# deska.net
KiCad netlist of a schematic drawn in EAGLE
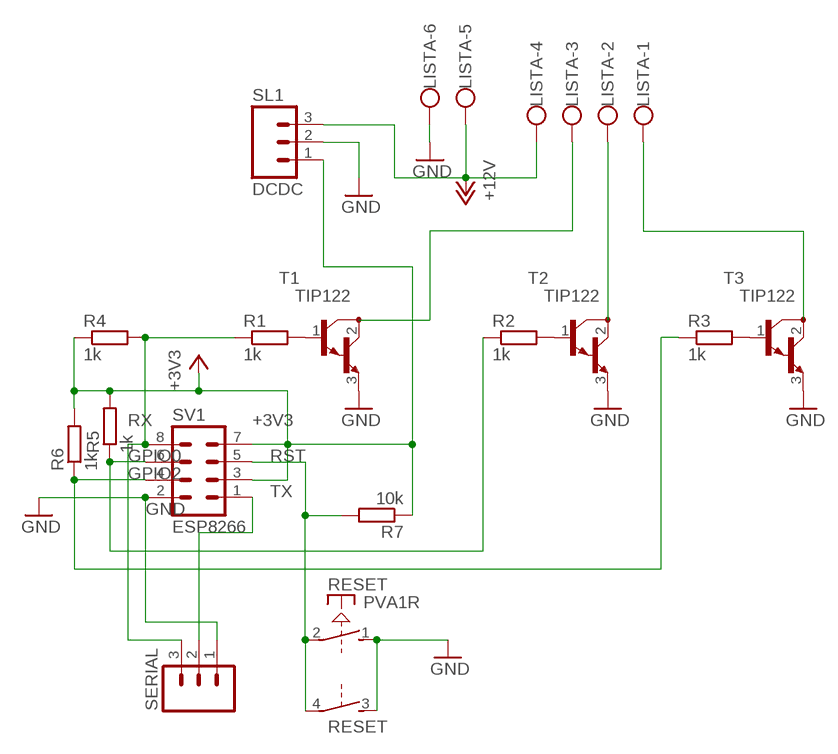
[diagram p0: schematic, sheet 1]

(export (version "E")
  (design (tool "Eeschema 10.0.6"))
  (components
    (comp (ref "LISTA")
      (value "W237-6")
      (footprint "eagle-import:W237-6")
      (libsource (lib "eagle-import") (part "W237-6"))
    )
    (comp (ref "R1")
      (value "1k")
      (footprint "eagle-import:0207_10")
      (libsource (lib "eagle-import") (part "R-EU_0207/10"))
    )
    (comp (ref "R2")
      (value "1k")
      (footprint "eagle-import:0207_10")
      (libsource (lib "eagle-import") (part "R-EU_0207/10"))
    )
    (comp (ref "R3")
      (value "1k")
      (footprint "eagle-import:0207_10")
      (libsource (lib "eagle-import") (part "R-EU_0207/10"))
    )
    (comp (ref "R4")
      (value "1k")
      (footprint "eagle-import:0207_10")
      (libsource (lib "eagle-import") (part "R-EU_0207/10"))
    )
    (comp (ref "R5")
      (value "1k")
      (footprint "eagle-import:0207_10")
      (libsource (lib "eagle-import") (part "R-EU_0207/10"))
    )
    (comp (ref "R6")
      (value "1k")
      (footprint "eagle-import:0207_10")
      (libsource (lib "eagle-import") (part "R-EU_0207/10"))
    )
    (comp (ref "R7")
      (value "10k")
      (footprint "eagle-import:0207_10")
      (libsource (lib "eagle-import") (part "R-EU_0207/10"))
    )
    (comp (ref "RESET")
      (value "PVA1R")
      (footprint "eagle-import:PVA1R")
      (libsource (lib "eagle-import") (part "PVA1R"))
    )
    (comp (ref "SERIAL")
      (value "M03")
      (footprint "eagle-import:03P")
      (libsource (lib "eagle-import") (part "M03"))
    )
    (comp (ref "SL1")
      (value "DCDC")
      (footprint "eagle-import:03P")
      (libsource (lib "eagle-import") (part "M03"))
    )
    (comp (ref "SV1")
      (value "ESP8266")
      (footprint "eagle-import:MA04-2")
      (libsource (lib "eagle-import") (part "MA04-2"))
    )
    (comp (ref "T1")
      (value "TIP122")
      (footprint "eagle-import:TO220")
      (libsource (lib "eagle-import") (part "TIP122"))
    )
    (comp (ref "T2")
      (value "TIP122")
      (footprint "eagle-import:TO220")
      (libsource (lib "eagle-import") (part "TIP122"))
    )
    (comp (ref "T3")
      (value "TIP122")
      (footprint "eagle-import:TO220")
      (libsource (lib "eagle-import") (part "TIP122"))
    )
  )
  (nets
    (net (code "1") (name "+3V3") (class "Default")
      (node (ref "R4") (pin "1") (pinfunction "1_1") (pintype "passive"))
      (node (ref "R5") (pin "2") (pinfunction "2_2") (pintype "passive"))
      (node (ref "R6") (pin "2") (pinfunction "2_2") (pintype "passive"))
      (node (ref "R7") (pin "1") (pinfunction "1_1") (pintype "passive"))
      (node (ref "SL1") (pin "1") (pinfunction "1_1") (pintype "passive"))
      (node (ref "SV1") (pin "3") (pinfunction "3_3") (pintype "passive"))
      (node (ref "SV1") (pin "7") (pinfunction "7_7") (pintype "passive"))
    )
    (net (code "2") (name "+12V") (class "Default")
      (node (ref "LISTA") (pin "4") (pinfunction "KL_4") (pintype "passive"))
      (node (ref "LISTA") (pin "5") (pinfunction "KL_5") (pintype "passive"))
      (node (ref "SL1") (pin "3") (pinfunction "3_3") (pintype "passive"))
    )
    (net (code "3") (name "/GPIO0") (class "Default")
      (node (ref "R2") (pin "1") (pinfunction "1_1") (pintype "passive"))
      (node (ref "R5") (pin "1") (pinfunction "1_1") (pintype "passive"))
      (node (ref "SV1") (pin "6") (pinfunction "6_6") (pintype "passive"))
    )
    (net (code "4") (name "/GPIO2") (class "Default")
      (node (ref "R3") (pin "1") (pinfunction "1_1") (pintype "passive"))
      (node (ref "R6") (pin "1") (pinfunction "1_1") (pintype "passive"))
      (node (ref "SV1") (pin "4") (pinfunction "4_4") (pintype "passive"))
    )
    (net (code "5") (name "/RST") (class "Default")
      (node (ref "R7") (pin "2") (pinfunction "2_2") (pintype "passive"))
      (node (ref "RESET") (pin "2") (pinfunction "P_2") (pintype "passive"))
      (node (ref "RESET") (pin "4") (pinfunction "P_4") (pintype "passive"))
      (node (ref "SV1") (pin "5") (pinfunction "5_5") (pintype "passive"))
    )
    (net (code "6") (name "/RX") (class "Default")
      (node (ref "R1") (pin "1") (pinfunction "1_1") (pintype "passive"))
      (node (ref "R4") (pin "2") (pinfunction "2_2") (pintype "passive"))
      (node (ref "SERIAL") (pin "3") (pinfunction "3_3") (pintype "passive"))
      (node (ref "SV1") (pin "8") (pinfunction "8_8") (pintype "passive"))
    )
    (net (code "7") (name "/TX") (class "Default")
      (node (ref "SERIAL") (pin "2") (pinfunction "2_2") (pintype "passive"))
      (node (ref "SV1") (pin "1") (pinfunction "1_1") (pintype "passive"))
    )
    (net (code "8") (name "GND") (class "Default")
      (node (ref "LISTA") (pin "6") (pinfunction "KL_6") (pintype "passive"))
      (node (ref "RESET") (pin "1") (pinfunction "S_1") (pintype "passive"))
      (node (ref "RESET") (pin "3") (pinfunction "S_3") (pintype "passive"))
      (node (ref "SERIAL") (pin "1") (pinfunction "1_1") (pintype "passive"))
      (node (ref "SL1") (pin "2") (pinfunction "2_2") (pintype "passive"))
      (node (ref "SV1") (pin "2") (pinfunction "2_2") (pintype "passive"))
      (node (ref "T1") (pin "3") (pinfunction "E_3") (pintype "passive"))
      (node (ref "T2") (pin "3") (pinfunction "E_3") (pintype "passive"))
      (node (ref "T3") (pin "3") (pinfunction "E_3") (pintype "passive"))
    )
    (net (code "9") (name "Net-(LISTAA-KL)") (class "Default")
      (node (ref "LISTA") (pin "1") (pinfunction "KL_1") (pintype "passive"))
      (node (ref "T3") (pin "2") (pinfunction "C_2") (pintype "passive"))
    )
    (net (code "10") (name "Net-(LISTAB-KL)") (class "Default")
      (node (ref "LISTA") (pin "2") (pinfunction "KL_2") (pintype "passive"))
      (node (ref "T2") (pin "2") (pinfunction "C_2") (pintype "passive"))
    )
    (net (code "11") (name "Net-(LISTAC-KL)") (class "Default")
      (node (ref "LISTA") (pin "3") (pinfunction "KL_3") (pintype "passive"))
      (node (ref "T1") (pin "2") (pinfunction "C_2") (pintype "passive"))
    )
    (net (code "12") (name "Net-(T1-B)") (class "Default")
      (node (ref "R1") (pin "2") (pinfunction "2_2") (pintype "passive"))
      (node (ref "T1") (pin "1") (pinfunction "B_1") (pintype "passive"))
    )
    (net (code "13") (name "Net-(T2-B)") (class "Default")
      (node (ref "R2") (pin "2") (pinfunction "2_2") (pintype "passive"))
      (node (ref "T2") (pin "1") (pinfunction "B_1") (pintype "passive"))
    )
    (net (code "14") (name "Net-(T3-B)") (class "Default")
      (node (ref "R3") (pin "2") (pinfunction "2_2") (pintype "passive"))
      (node (ref "T3") (pin "1") (pinfunction "B_1") (pintype "passive"))
    )
  )
)
